# RC-CAR-Rx.net
KiCad netlist of a schematic drawn in EasyEDA
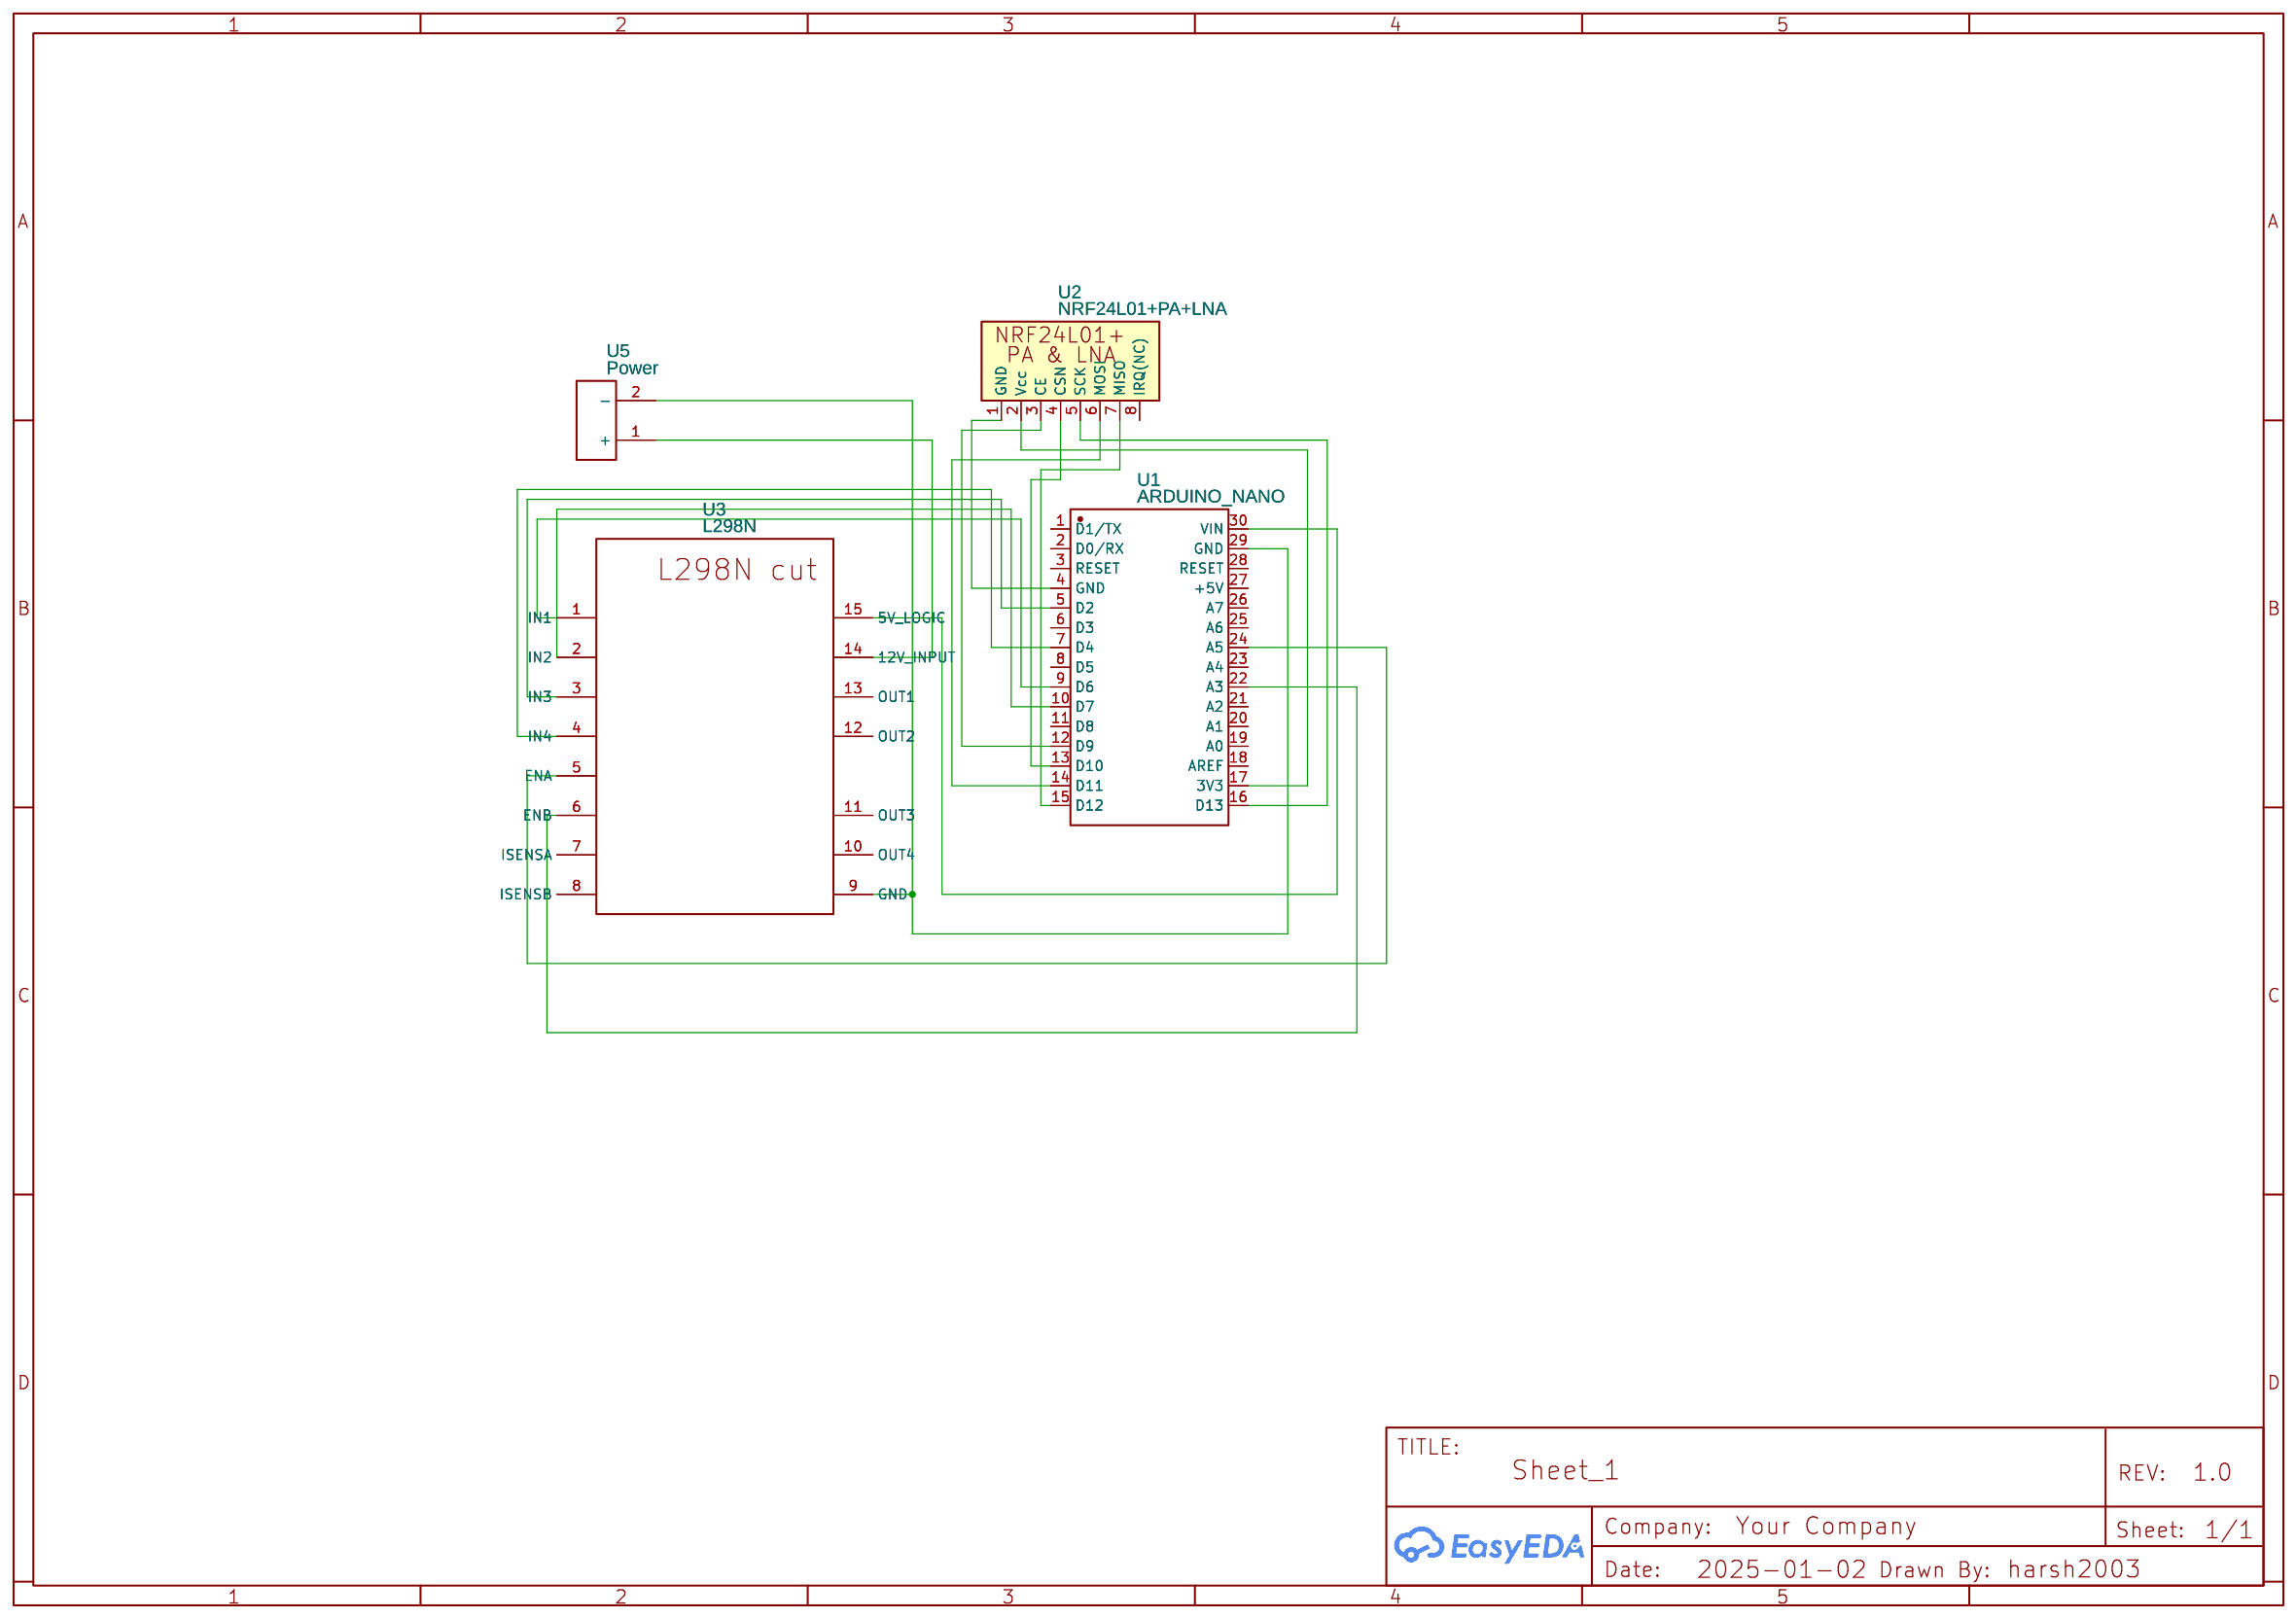
[diagram p0: schematic sheet]

(export (version "E")
  (design (tool "Eeschema 10.0.6"))
  (components
    (comp (ref "U1") (value "ARDUINO_NANO") (libsource (lib "") (part "ARDUINO_NANO")))
    (comp (ref "U2")
      (value "NRF24L01+PA+LNA")
      (fields (field (name "Manufacturer Part") "NRF24L01+") (field (name "Manufacturer") "Fo2sh"))
      (libsource (lib "") (part "AR_NRF24L01+PA+LNA"))
    )
    (comp (ref "U3") (value "L298N") (libsource (lib "") (part "cutl298")))
    (comp (ref "U5") (value "Power") (libsource (lib "") (part "RpiPowerUSBcableConnector")))
  )
  (nets
    (net (code "1") (name "Net-(U1-3V3)") (class "Default")
      (node (ref "U1") (pin "17") (pinfunction "3V3_17") (pintype "unspecified"))
      (node (ref "U2") (pin "2") (pinfunction "Vcc_2") (pintype "unspecified"))
    )
    (net (code "2") (name "Net-(U1-A3)") (class "Default")
      (node (ref "U1") (pin "22") (pinfunction "A3_22") (pintype "unspecified"))
      (node (ref "U3") (pin "6") (pinfunction "ENB_6") (pintype "unspecified"))
    )
    (net (code "3") (name "Net-(U1-A5)") (class "Default")
      (node (ref "U1") (pin "24") (pinfunction "A5_24") (pintype "unspecified"))
      (node (ref "U3") (pin "5") (pinfunction "ENA_5") (pintype "unspecified"))
    )
    (net (code "4") (name "Net-(U1-D2)") (class "Default")
      (node (ref "U1") (pin "5") (pinfunction "D2_5") (pintype "unspecified"))
      (node (ref "U3") (pin "3") (pinfunction "IN3_3") (pintype "unspecified"))
    )
    (net (code "5") (name "Net-(U1-D4)") (class "Default")
      (node (ref "U1") (pin "7") (pinfunction "D4_7") (pintype "unspecified"))
      (node (ref "U3") (pin "4") (pinfunction "IN4_4") (pintype "unspecified"))
    )
    (net (code "6") (name "Net-(U1-D6)") (class "Default")
      (node (ref "U1") (pin "9") (pinfunction "D6_9") (pintype "unspecified"))
      (node (ref "U3") (pin "1") (pinfunction "IN1_1") (pintype "unspecified"))
    )
    (net (code "7") (name "Net-(U1-D7)") (class "Default")
      (node (ref "U1") (pin "10") (pinfunction "D7_10") (pintype "unspecified"))
      (node (ref "U3") (pin "2") (pinfunction "IN2_2") (pintype "unspecified"))
    )
    (net (code "8") (name "Net-(U1-D9)") (class "Default")
      (node (ref "U1") (pin "12") (pinfunction "D9_12") (pintype "unspecified"))
      (node (ref "U2") (pin "3") (pinfunction "CE_3") (pintype "unspecified"))
    )
    (net (code "9") (name "Net-(U1-D10)") (class "Default")
      (node (ref "U1") (pin "13") (pinfunction "D10_13") (pintype "unspecified"))
      (node (ref "U2") (pin "4") (pinfunction "CSN_4") (pintype "unspecified"))
    )
    (net (code "10") (name "Net-(U1-D11)") (class "Default")
      (node (ref "U1") (pin "14") (pinfunction "D11_14") (pintype "unspecified"))
      (node (ref "U2") (pin "6") (pinfunction "MOSI_6") (pintype "unspecified"))
    )
    (net (code "11") (name "Net-(U1-D12)") (class "Default")
      (node (ref "U1") (pin "15") (pinfunction "D12_15") (pintype "unspecified"))
      (node (ref "U2") (pin "7") (pinfunction "MISO_7") (pintype "unspecified"))
    )
    (net (code "12") (name "Net-(U1-D13)") (class "Default")
      (node (ref "U1") (pin "16") (pinfunction "D13_16") (pintype "unspecified"))
      (node (ref "U2") (pin "5") (pinfunction "SCK_5") (pintype "unspecified"))
    )
    (net (code "13") (name "Net-(U1-VIN)") (class "Default")
      (node (ref "U1") (pin "30") (pinfunction "VIN_30") (pintype "unspecified"))
      (node (ref "U3") (pin "15") (pinfunction "5V_LOGIC_15") (pintype "unspecified"))
    )
    (net (code "14") (name "Net-(U2-GND)") (class "Default")
      (node (ref "U1") (pin "4") (pinfunction "GND_4") (pintype "unspecified"))
      (node (ref "U2") (pin "1") (pinfunction "GND_1") (pintype "unspecified"))
    )
    (net (code "15") (name "Net-(U3-12V_INPUT)") (class "Default")
      (node (ref "U3") (pin "14") (pinfunction "12V_INPUT_14") (pintype "unspecified"))
      (node (ref "U5") (pin "1") (pinfunction "+_1") (pintype "unspecified"))
    )
    (net (code "16") (name "Net-(U3-GND)") (class "Default")
      (node (ref "U1") (pin "29") (pinfunction "GND_29") (pintype "unspecified"))
      (node (ref "U3") (pin "9") (pinfunction "GND_9") (pintype "unspecified"))
      (node (ref "U5") (pin "2") (pinfunction "-_2") (pintype "unspecified"))
    )
    (net (code "17") (name "unconnected-(U1-+5V-Pad27)") (class "Default")
      (node (ref "U1") (pin "27") (pinfunction "+5V_27") (pintype "unspecified"))
    )
    (net (code "18") (name "unconnected-(U1-A0-Pad19)") (class "Default")
      (node (ref "U1") (pin "19") (pinfunction "A0_19") (pintype "unspecified"))
    )
    (net (code "19") (name "unconnected-(U1-A1-Pad20)") (class "Default")
      (node (ref "U1") (pin "20") (pinfunction "A1_20") (pintype "unspecified"))
    )
    (net (code "20") (name "unconnected-(U1-A2-Pad21)") (class "Default")
      (node (ref "U1") (pin "21") (pinfunction "A2_21") (pintype "unspecified"))
    )
    (net (code "21") (name "unconnected-(U1-A4-Pad23)") (class "Default")
      (node (ref "U1") (pin "23") (pinfunction "A4_23") (pintype "unspecified"))
    )
    (net (code "22") (name "unconnected-(U1-A6-Pad25)") (class "Default")
      (node (ref "U1") (pin "25") (pinfunction "A6_25") (pintype "unspecified"))
    )
    (net (code "23") (name "unconnected-(U1-A7-Pad26)") (class "Default")
      (node (ref "U1") (pin "26") (pinfunction "A7_26") (pintype "unspecified"))
    )
    (net (code "24") (name "unconnected-(U1-AREF-Pad18)") (class "Default")
      (node (ref "U1") (pin "18") (pinfunction "AREF_18") (pintype "unspecified"))
    )
    (net (code "25") (name "unconnected-(U1-D0{slash}RX-Pad2)") (class "Default")
      (node (ref "U1") (pin "2") (pinfunction "D0/RX_2") (pintype "unspecified"))
    )
    (net (code "26") (name "unconnected-(U1-D1{slash}TX-Pad1)") (class "Default")
      (node (ref "U1") (pin "1") (pinfunction "D1/TX_1") (pintype "unspecified"))
    )
    (net (code "27") (name "unconnected-(U1-D3-Pad6)") (class "Default")
      (node (ref "U1") (pin "6") (pinfunction "D3_6") (pintype "unspecified"))
    )
    (net (code "28") (name "unconnected-(U1-D5-Pad8)") (class "Default")
      (node (ref "U1") (pin "8") (pinfunction "D5_8") (pintype "unspecified"))
    )
    (net (code "29") (name "unconnected-(U1-D8-Pad11)") (class "Default")
      (node (ref "U1") (pin "11") (pinfunction "D8_11") (pintype "unspecified"))
    )
    (net (code "30") (name "unconnected-(U1-RESET-Pad3)") (class "Default")
      (node (ref "U1") (pin "3") (pinfunction "RESET_3") (pintype "unspecified"))
    )
    (net (code "31") (name "unconnected-(U1-RESET-Pad28)") (class "Default")
      (node (ref "U1") (pin "28") (pinfunction "RESET_28") (pintype "unspecified"))
    )
    (net (code "32") (name "unconnected-(U2-IRQ(NC)-Pad8)") (class "Default")
      (node (ref "U2") (pin "8") (pinfunction "IRQ(NC)_8") (pintype "unspecified"))
    )
    (net (code "33") (name "unconnected-(U3-ISENSA-Pad7)") (class "Default")
      (node (ref "U3") (pin "7") (pinfunction "ISENSA_7") (pintype "unspecified"))
    )
    (net (code "34") (name "unconnected-(U3-ISENSB-Pad8)") (class "Default")
      (node (ref "U3") (pin "8") (pinfunction "ISENSB_8") (pintype "unspecified"))
    )
    (net (code "35") (name "unconnected-(U3-OUT1-Pad13)") (class "Default")
      (node (ref "U3") (pin "13") (pinfunction "OUT1_13") (pintype "unspecified"))
    )
    (net (code "36") (name "unconnected-(U3-OUT2-Pad12)") (class "Default")
      (node (ref "U3") (pin "12") (pinfunction "OUT2_12") (pintype "unspecified"))
    )
    (net (code "37") (name "unconnected-(U3-OUT3-Pad11)") (class "Default")
      (node (ref "U3") (pin "11") (pinfunction "OUT3_11") (pintype "unspecified"))
    )
    (net (code "38") (name "unconnected-(U3-OUT4-Pad10)") (class "Default")
      (node (ref "U3") (pin "10") (pinfunction "OUT4_10") (pintype "unspecified"))
    )
  )
)
